# PressureSensor.net
KiCad netlist of a schematic drawn in Altium Designer
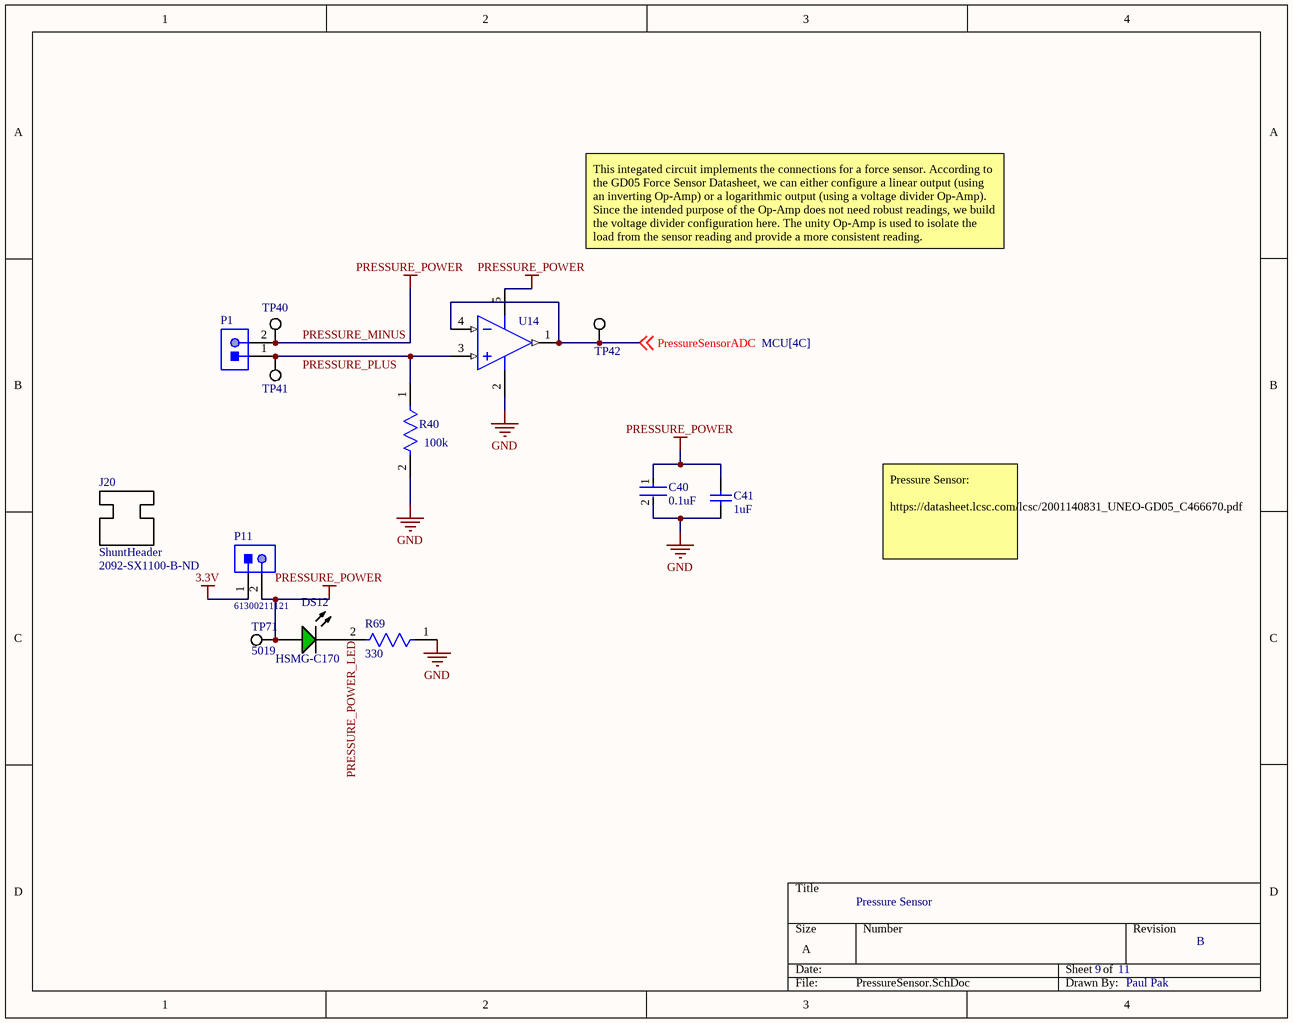
[diagram p0: PressureSensor.SchDoc]

(export (version "E")
  (design (tool "Eeschema 10.0.6"))
  (components
    (comp (ref "C40")
      (value "0.1uF")
      (footprint "FP-CC0805-0_85-MFG")
      (description "CAP CER 0.1UF 25V X7R 0805")
      (fields (field (name "MANUFACTURER PART NUMBER") "CC0805KRX7R8BB104") (field (name "TOLERANCE") "0.1"))
      (libsource (lib "Altium Content Vault") (part "11868f565c42a9108669ba33697ecf6"))
    )
    (comp (ref "C41")
      (value "1uF")
      (footprint "CAPC2013X145X50ML20T25")
      (fields
        (field (name "PART NUMBER") "CC0805ZRY5V8BB105")
        (field (name "MANUFACTURER") "Yageo")
        (field (name "TOLERANCE") "80%")
      )
      (libsource (lib "Altium Content Vault") (part "CAP"))
    )
    (comp (ref "DS12")
      (value "HSMG-C170")
      (footprint "AVAG-HSMX-C170_V")
      (description "Chip LED, Green, 2.2 V, -40 to 85 degC, 2-Pin SMD, Pb-Free, Tape and Reel")
      (fields (field (name "MANUFACTURER") "Avago"))
      (libsource (lib "Altium Content Vault") (part "LED_GREEN_A1K2-2"))
    )
    (comp (ref "J20")
      (value "ShuntHeader")
      (description "Conn Mini Shunt 2 POS 2.54mm Black Cable Mount")
      (fields
        (field (name "MANUFACTURER") "Kycon")
        (field (name "MANUFACTURER PART NUMBER") "SX1100-B")
        (field (name "SUPPLIER PART NUMBER 1") "2092-SX1100-B-ND")
      )
      (libsource (lib "CustomSchematics") (part "ShuntHeader"))
    )
    (comp (ref "P1")
      (value "61300211121")
      (footprint "61300211121")
      (description "THT Vertical Pin Header WR-PHD, Pitch 2.54 mm, Single Row, 2 pins")
      (fields (field (name "MANUFACTURER") "Wurth Elektronik") (field (name "PUBLISHER") "WurthElektronik"))
      (libsource (lib "Altium Content Vault") (part "WE-CN-1P-M-R2"))
    )
    (comp (ref "P11")
      (value "61300211121")
      (footprint "61300211121")
      (description "THT Vertical Pin Header WR-PHD, Pitch 2.54 mm, Single Row, 2 pins")
      (fields (field (name "MANUFACTURER") "Wurth Elektronik") (field (name "PUBLISHER") "WurthElektronik"))
      (libsource (lib "") (part "WE-CN-1P-M-R2_1"))
    )
    (comp (ref "R40")
      (value "100k")
      (footprint "FP-ERA6A-IPC_B")
      (description "RES 100K OHM 0.1% 1/8W 0805")
      (fields (field (name "TOLERANCE") "0.1%") (field (name "MANUFACTURER") "Panasonic"))
      (libsource (lib "Altium Content Vault") (part "1029c3af85768c4190bb7ad29bc67b5"))
    )
    (comp (ref "R69")
      (value "330")
      (footprint "FP-CRCW0805-e3-MFG")
      (description "RES Thick Film, 330Ω, 1%, 0.125W, 100ppm/°C, 0805")
      (fields (field (name "TOLERANCE") "1%") (field (name "MANUFACTURER") "Vishay"))
      (libsource (lib "Altium Content Vault") (part "1029c3af85768c4190bb7ad29bc67b5"))
    )
    (comp (ref "TP40")
      (value "5019")
      (footprint "KSTN-5019_V")
      (description "Test Point, 1 Position SMD, RoHS, Tape and Reel")
      (fields (field (name "MANUFACTURER") "Keystone Electronics"))
      (libsource (lib "Altium Content Vault") (part "TESTPOINT_WHITE"))
    )
    (comp (ref "TP41")
      (value "5019")
      (footprint "KSTN-5019_V")
      (description "Test Point, 1 Position SMD, RoHS, Tape and Reel")
      (fields (field (name "MANUFACTURER") "Keystone Electronics"))
      (libsource (lib "Altium Content Vault") (part "TESTPOINT_WHITE"))
    )
    (comp (ref "TP42")
      (value "5019")
      (footprint "KSTN-5019_V")
      (description "Test Point, 1 Position SMD, RoHS, Tape and Reel")
      (fields (field (name "MANUFACTURER") "Keystone Electronics"))
      (libsource (lib "Altium Content Vault") (part "TESTPOINT_WHITE"))
    )
    (comp (ref "TP71")
      (value "5019")
      (footprint "KSTN-5019_V")
      (description "Test Point, 1 Position SMD, RoHS, Tape and Reel")
      (fields (field (name "MANUFACTURER") "Keystone Electronics"))
      (libsource (lib "Altium Content Vault") (part "TESTPOINT_WHITE"))
    )
    (comp (ref "U14")
      (value "LMV796QMF/NOPB")
      (footprint "DBV0005A_L")
      (fields (field (name "MANUFACTURER") "Texas Instruments"))
      (libsource (lib "Altium Content Vault") (part "AMP-OPA-LM7121-5"))
    )
  )
  (nets
    (net (code "1") (name "/PRESSURE_PLUS") (class "Default")
      (node (ref "P1") (pin "1") (pinfunction "1_1") (pintype "passive"))
      (node (ref "R40") (pin "1") (pinfunction "1_1") (pintype "passive"))
      (node (ref "TP41") (pin "1") (pinfunction "1_1") (pintype "passive"))
      (node (ref "U14") (pin "3") (pinfunction "IN+_3") (pintype "input"))
    )
    (net (code "2") (name "/PRESSURE_POWER_LED") (class "Default")
      (node (ref "DS12") (pin "2") (pinfunction "K_2") (pintype "passive"))
      (node (ref "R69") (pin "2") (pinfunction "2_2") (pintype "passive"))
    )
    (net (code "3") (name "3.3V") (class "Default")
      (node (ref "P11") (pin "1") (pinfunction "1_1") (pintype "passive"))
    )
    (net (code "4") (name "GND") (class "Default")
      (node (ref "C40") (pin "2") (pinfunction "2_2") (pintype "passive"))
      (node (ref "C41") (pin "1") (pinfunction "1_1") (pintype "passive"))
      (node (ref "R40") (pin "2") (pinfunction "2_2") (pintype "passive"))
      (node (ref "R69") (pin "1") (pinfunction "1_1") (pintype "passive"))
      (node (ref "U14") (pin "2") (pinfunction "V-_2") (pintype "power_in"))
    )
    (net (code "5") (name "PRESSURE_POWER") (class "Default")
      (node (ref "C40") (pin "1") (pinfunction "1_1") (pintype "passive"))
      (node (ref "C41") (pin "2") (pinfunction "2_2") (pintype "passive"))
      (node (ref "DS12") (pin "1") (pinfunction "A_1") (pintype "passive"))
      (node (ref "P1") (pin "2") (pinfunction "2_2") (pintype "passive"))
      (node (ref "P11") (pin "2") (pinfunction "2_2") (pintype "passive"))
      (node (ref "TP40") (pin "1") (pinfunction "1_1") (pintype "passive"))
      (node (ref "TP71") (pin "1") (pinfunction "1_1") (pintype "passive"))
      (node (ref "U14") (pin "5") (pinfunction "V+_5") (pintype "power_in"))
    )
    (net (code "6") (name "PressureSensorADC") (class "Default")
      (node (ref "TP42") (pin "1") (pinfunction "1_1") (pintype "passive"))
      (node (ref "U14") (pin "1") (pinfunction "OUT_1") (pintype "output"))
      (node (ref "U14") (pin "4") (pinfunction "IN-_4") (pintype "input"))
    )
  )
)
